# PAGE3-LED_Drivers.net
KiCad netlist of a schematic drawn in Altium Designer
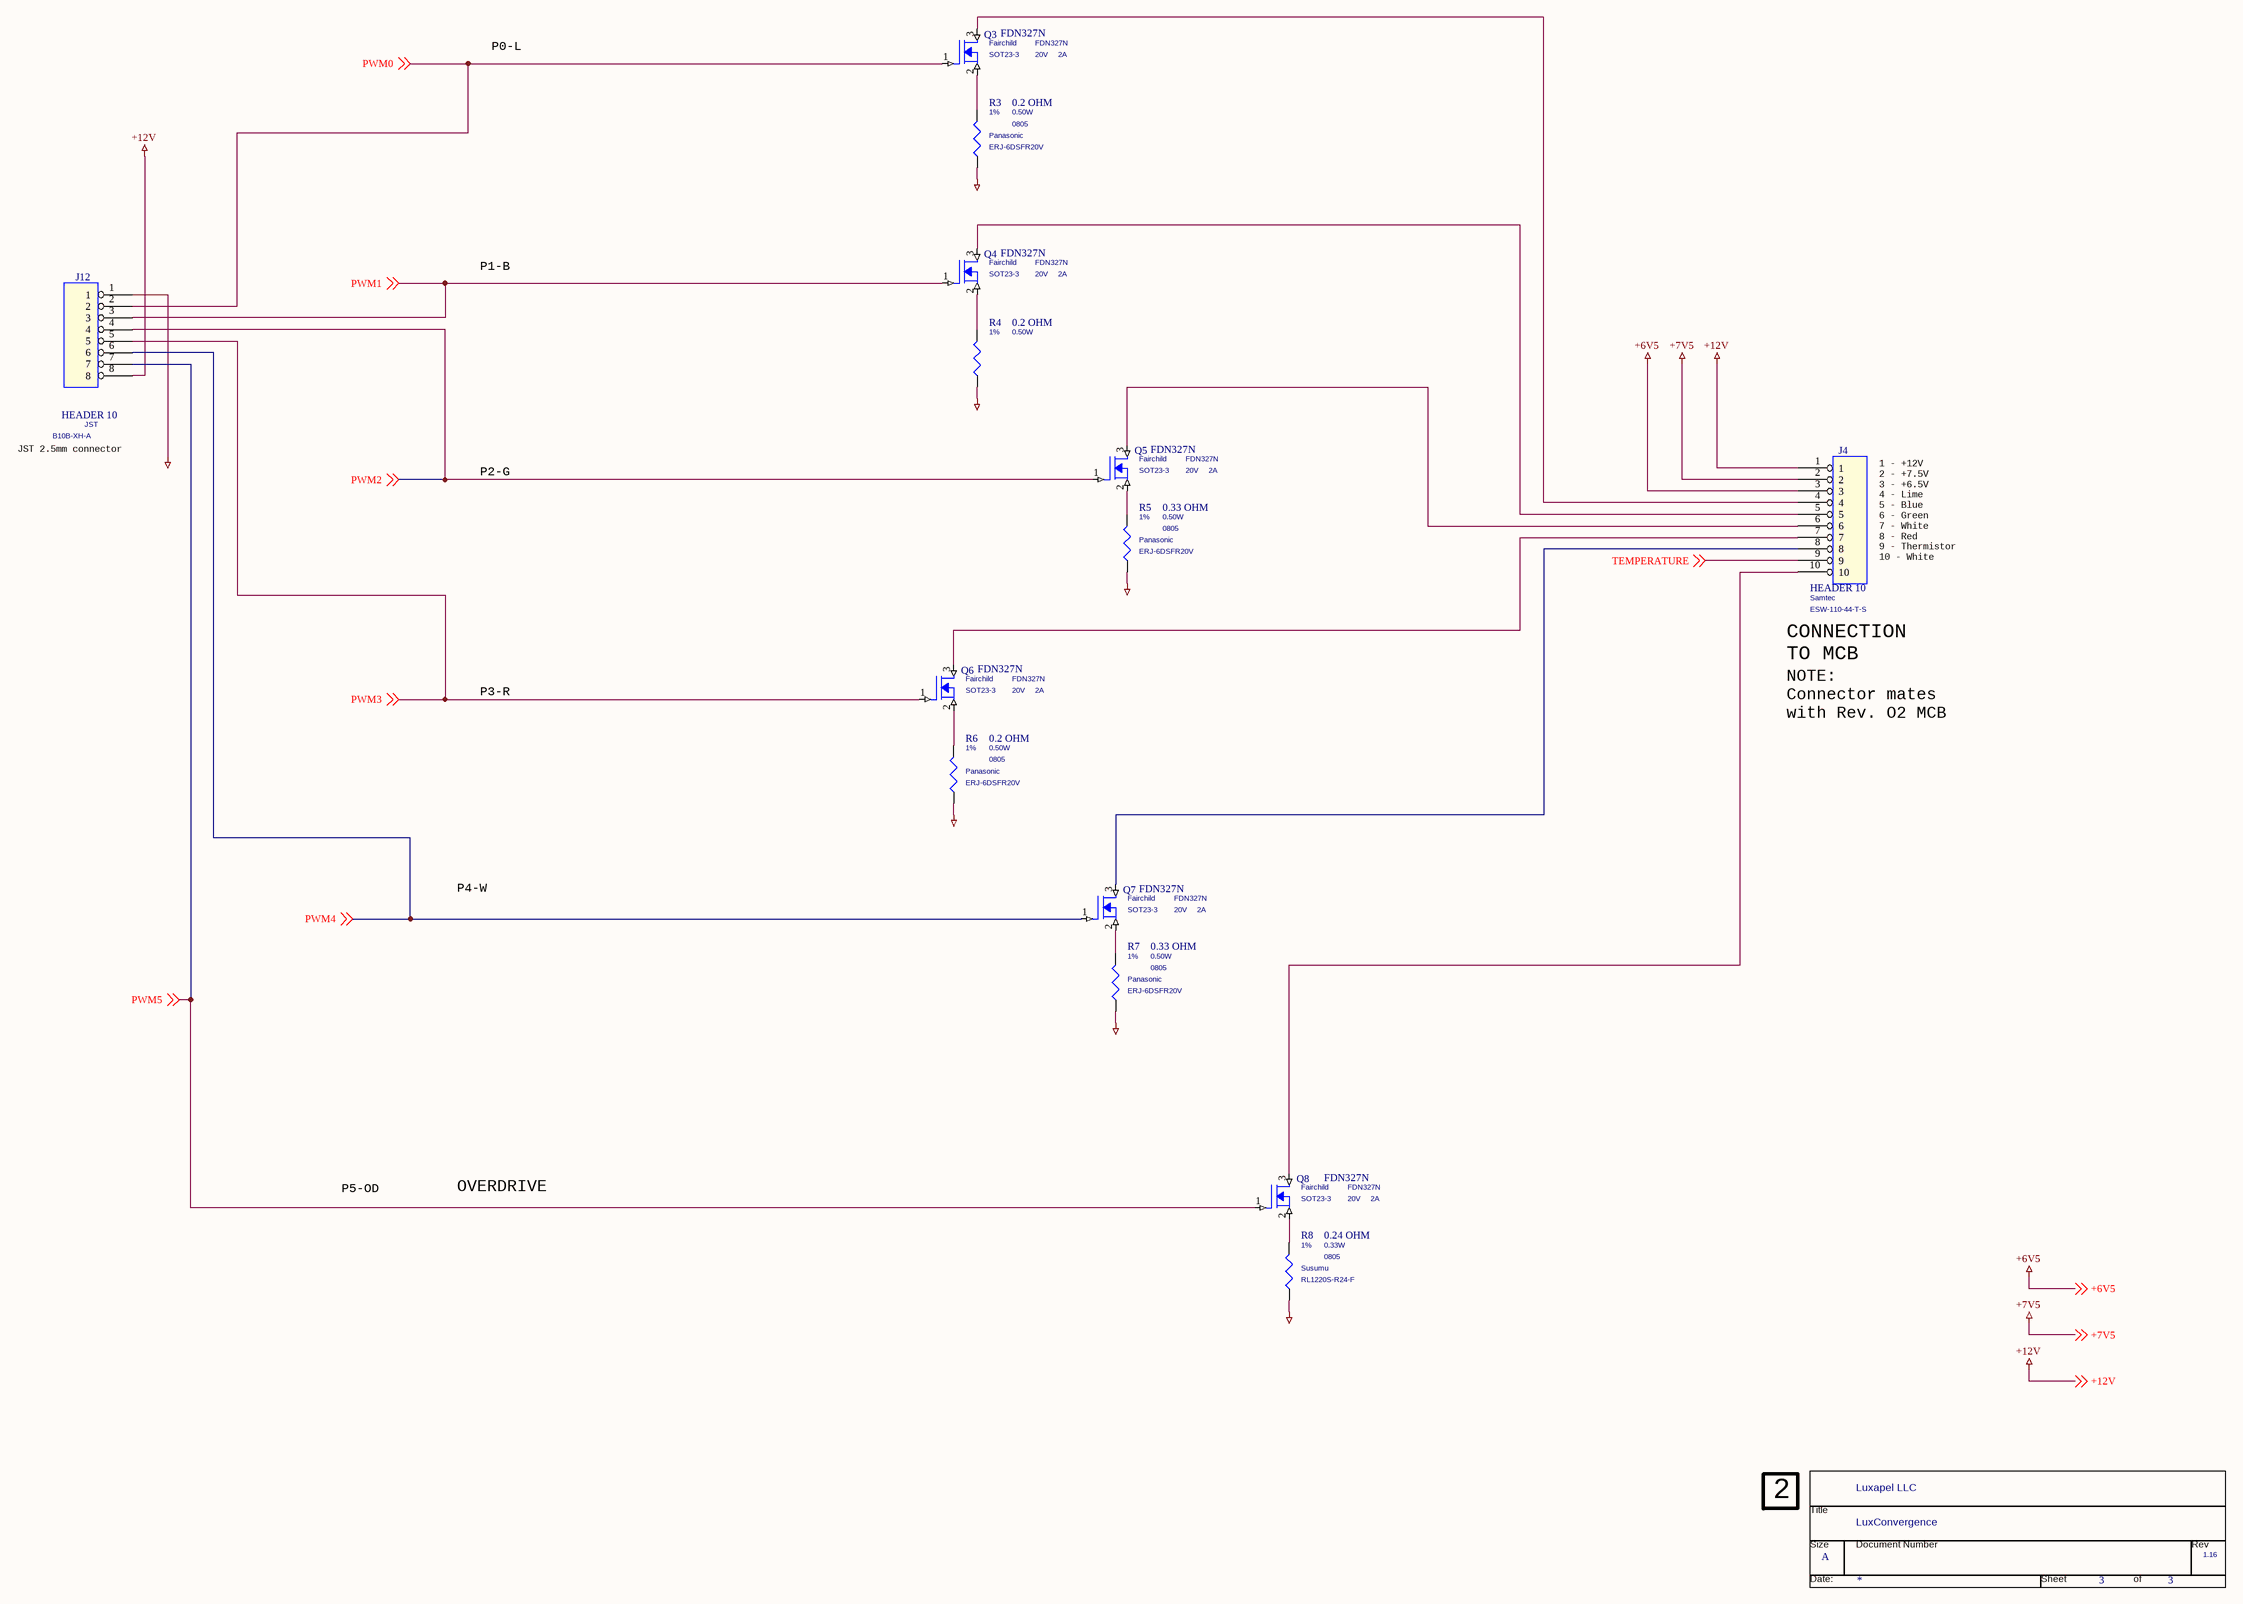
[diagram p0: PAGE3-LED_Drivers.SchDoc]

(export (version "E")
  (design (tool "Eeschema 10.0.6"))
  (components
    (comp (ref "J4")
      (value "HEADER 10")
      (footprint "SIP-10")
      (fields (field (name "MFG") "Samtec") (field (name "P/N") "ESW-110-44-T-S"))
      (libsource (lib "*") (part "HEADER 10"))
    )
    (comp (ref "J12")
      (value "HEADER 10")
      (footprint "SIP-10")
      (fields (field (name "MFG") "JST") (field (name "P/N") "B10B-XH-A"))
      (libsource (lib "*") (part "HEADER 10_0"))
    )
    (comp (ref "Q3")
      (value "FDN327N")
      (footprint "SOT23-3")
      (fields
        (field (name "VOLTAGE") "20V")
        (field (name "POWER") "2A")
        (field (name "P/N") "FDN327N")
        (field (name "MFG") "Fairchild")
        (field (name "PCB FOOTPRINT") "SOT23-3")
      )
      (libsource (lib "*") (part "N DGS_0"))
    )
    (comp (ref "Q4")
      (value "FDN327N")
      (footprint "SOT23-3")
      (fields
        (field (name "VOLTAGE") "20V")
        (field (name "POWER") "2A")
        (field (name "P/N") "FDN327N")
        (field (name "MFG") "Fairchild")
        (field (name "PCB FOOTPRINT") "SOT23-3")
      )
      (libsource (lib "*") (part "N DGS_0"))
    )
    (comp (ref "Q5")
      (value "FDN327N")
      (footprint "SOT23-3")
      (fields
        (field (name "MFG") "Fairchild")
        (field (name "P/N") "FDN327N")
        (field (name "POWER") "2A")
        (field (name "VOLTAGE") "20V")
        (field (name "PCB FOOTPRINT") "SOT23-3")
      )
      (libsource (lib "*") (part "N DGS_0"))
    )
    (comp (ref "Q6")
      (value "FDN327N")
      (footprint "SOT23-3")
      (fields
        (field (name "MFG") "Fairchild")
        (field (name "P/N") "FDN327N")
        (field (name "POWER") "2A")
        (field (name "VOLTAGE") "20V")
        (field (name "PCB FOOTPRINT") "SOT23-3")
      )
      (libsource (lib "*") (part "N DGS_0"))
    )
    (comp (ref "Q7")
      (value "FDN327N")
      (footprint "SOT23-323")
      (fields
        (field (name "MFG") "Fairchild")
        (field (name "P/N") "FDN327N")
        (field (name "POWER") "2A")
        (field (name "VOLTAGE") "20V")
        (field (name "PCB FOOTPRINT") "SOT23-3")
      )
      (libsource (lib "*") (part "N DGS_0"))
    )
    (comp (ref "Q8")
      (value "FDN327N")
      (footprint "SOT23-3")
      (fields
        (field (name "VOLTAGE") "20V")
        (field (name "POWER") "2A")
        (field (name "P/N") "FDN327N")
        (field (name "MFG") "Fairchild")
        (field (name "PCB FOOTPRINT") "SOT23-3")
      )
      (libsource (lib "*") (part "N DGS_0"))
    )
    (comp (ref "R3")
      (value "0.2 OHM")
      (footprint "0805")
      (fields
        (field (name "MFG") "Panasonic")
        (field (name "P/N") "ERJ-6DSFR20V")
        (field (name "PRECISION") "1%")
        (field (name "POWER") "0.50W")
        (field (name "VOLTAGE") "?V")
        (field (name "PCB FOOTPRINT") "0805")
      )
      (libsource (lib "*") (part "RESISTOR"))
    )
    (comp (ref "R4")
      (value "0.2 OHM")
      (footprint "1210")
      (fields
        (field (name "MFG") "Panasonic")
        (field (name "PRECISION") "1%")
        (field (name "POWER") "0.50W")
        (field (name "VOLTAGE") "?V")
      )
      (libsource (lib "*") (part "RESISTOR"))
    )
    (comp (ref "R5")
      (value "0.33 OHM")
      (footprint "_0805")
      (fields
        (field (name "MFG") "Panasonic")
        (field (name "P/N") "ERJ-6DSFR20V")
        (field (name "PRECISION") "1%")
        (field (name "POWER") "0.50W")
        (field (name "VOLTAGE") "?V")
        (field (name "PCB FOOTPRINT") "0805")
      )
      (libsource (lib "*") (part "RESISTOR"))
    )
    (comp (ref "R6")
      (value "0.2 OHM")
      (footprint "0805")
      (fields
        (field (name "MFG") "Panasonic")
        (field (name "P/N") "ERJ-6DSFR20V")
        (field (name "PRECISION") "1%")
        (field (name "POWER") "0.50W")
        (field (name "VOLTAGE") "?V")
        (field (name "PCB FOOTPRINT") "0805")
      )
      (libsource (lib "*") (part "RESISTOR"))
    )
    (comp (ref "R7")
      (value "0.33 OHM")
      (footprint "_0805")
      (fields
        (field (name "MFG") "Panasonic")
        (field (name "P/N") "ERJ-6DSFR20V")
        (field (name "PRECISION") "1%")
        (field (name "POWER") "0.50W")
        (field (name "VOLTAGE") "?V")
        (field (name "PCB FOOTPRINT") "0805")
      )
      (libsource (lib "*") (part "RESISTOR"))
    )
    (comp (ref "R8")
      (value "0.24 OHM")
      (footprint "0805")
      (fields
        (field (name "MFG") "Susumu")
        (field (name "P/N") "RL1220S-R24-F")
        (field (name "PRECISION") "1%")
        (field (name "POWER") "0.33W")
        (field (name "VOLTAGE") "?V")
        (field (name "PCB FOOTPRINT") "0805")
      )
      (libsource (lib "*") (part "RESISTOR"))
    )
  )
  (nets
    (net (code "1") (name "+6V5") (class "Default")
      (node (ref "J4") (pin "3") (pinfunction "3_3") (pintype "passive"))
    )
    (net (code "2") (name "+7V5") (class "Default")
      (node (ref "J4") (pin "2") (pinfunction "2_2") (pintype "passive"))
    )
    (net (code "3") (name "+12V") (class "Default")
      (node (ref "J12") (pin "8") (pinfunction "8_8") (pintype "passive"))
      (node (ref "J4") (pin "1") (pinfunction "1_1") (pintype "passive"))
    )
    (net (code "4") (name "GND_POWER.global") (class "Default")
      (node (ref "J12") (pin "1") (pinfunction "1_1") (pintype "passive"))
      (node (ref "R3") (pin "1") (pinfunction "1_1") (pintype "passive"))
      (node (ref "R4") (pin "1") (pinfunction "1_1") (pintype "passive"))
      (node (ref "R5") (pin "1") (pinfunction "1_1") (pintype "passive"))
      (node (ref "R6") (pin "1") (pinfunction "1_1") (pintype "passive"))
      (node (ref "R7") (pin "1") (pinfunction "1_1") (pintype "passive"))
      (node (ref "R8") (pin "1") (pinfunction "1_1") (pintype "passive"))
    )
    (net (code "5") (name "Net-(Q3-DRAIN)") (class "Default")
      (node (ref "J4") (pin "4") (pinfunction "4_4") (pintype "passive"))
      (node (ref "Q3") (pin "3") (pinfunction "DRAIN_3") (pintype "input"))
    )
    (net (code "6") (name "Net-(Q3-SOURCE)") (class "Default")
      (node (ref "Q3") (pin "2") (pinfunction "SOURCE_2") (pintype "input"))
      (node (ref "R3") (pin "2") (pinfunction "2_2") (pintype "passive"))
    )
    (net (code "7") (name "Net-(Q4-DRAIN)") (class "Default")
      (node (ref "J4") (pin "5") (pinfunction "5_5") (pintype "passive"))
      (node (ref "Q4") (pin "3") (pinfunction "DRAIN_3") (pintype "input"))
    )
    (net (code "8") (name "Net-(Q4-SOURCE)") (class "Default")
      (node (ref "Q4") (pin "2") (pinfunction "SOURCE_2") (pintype "input"))
      (node (ref "R4") (pin "2") (pinfunction "2_2") (pintype "passive"))
    )
    (net (code "9") (name "Net-(Q5-DRAIN)") (class "Default")
      (node (ref "J4") (pin "6") (pinfunction "6_6") (pintype "passive"))
      (node (ref "Q5") (pin "3") (pinfunction "DRAIN_3") (pintype "input"))
    )
    (net (code "10") (name "Net-(Q5-SOURCE)") (class "Default")
      (node (ref "Q5") (pin "2") (pinfunction "SOURCE_2") (pintype "input"))
      (node (ref "R5") (pin "2") (pinfunction "2_2") (pintype "passive"))
    )
    (net (code "11") (name "Net-(Q6-DRAIN)") (class "Default")
      (node (ref "J4") (pin "7") (pinfunction "7_7") (pintype "passive"))
      (node (ref "Q6") (pin "3") (pinfunction "DRAIN_3") (pintype "input"))
    )
    (net (code "12") (name "Net-(Q6-SOURCE)") (class "Default")
      (node (ref "Q6") (pin "2") (pinfunction "SOURCE_2") (pintype "input"))
      (node (ref "R6") (pin "2") (pinfunction "2_2") (pintype "passive"))
    )
    (net (code "13") (name "Net-(Q7-DRAIN)") (class "Default")
      (node (ref "J4") (pin "8") (pinfunction "8_8") (pintype "passive"))
      (node (ref "Q7") (pin "3") (pinfunction "DRAIN_3") (pintype "input"))
    )
    (net (code "14") (name "Net-(Q7-SOURCE)") (class "Default")
      (node (ref "Q7") (pin "2") (pinfunction "SOURCE_2") (pintype "input"))
      (node (ref "R7") (pin "2") (pinfunction "2_2") (pintype "passive"))
    )
    (net (code "15") (name "Net-(Q8-DRAIN)") (class "Default")
      (node (ref "J4") (pin "10") (pinfunction "10_10") (pintype "passive"))
      (node (ref "Q8") (pin "3") (pinfunction "DRAIN_3") (pintype "input"))
    )
    (net (code "16") (name "Net-(Q8-SOURCE)") (class "Default")
      (node (ref "Q8") (pin "2") (pinfunction "SOURCE_2") (pintype "input"))
      (node (ref "R8") (pin "2") (pinfunction "2_2") (pintype "passive"))
    )
    (net (code "17") (name "PWM0") (class "Default")
      (node (ref "J12") (pin "2") (pinfunction "2_2") (pintype "passive"))
      (node (ref "Q3") (pin "1") (pinfunction "GATE_1") (pintype "input"))
    )
    (net (code "18") (name "PWM1") (class "Default")
      (node (ref "J12") (pin "3") (pinfunction "3_3") (pintype "passive"))
      (node (ref "Q4") (pin "1") (pinfunction "GATE_1") (pintype "input"))
    )
    (net (code "19") (name "PWM2") (class "Default")
      (node (ref "J12") (pin "4") (pinfunction "4_4") (pintype "passive"))
      (node (ref "Q5") (pin "1") (pinfunction "GATE_1") (pintype "input"))
    )
    (net (code "20") (name "PWM3") (class "Default")
      (node (ref "J12") (pin "5") (pinfunction "5_5") (pintype "passive"))
      (node (ref "Q6") (pin "1") (pinfunction "GATE_1") (pintype "input"))
    )
    (net (code "21") (name "PWM4") (class "Default")
      (node (ref "J12") (pin "6") (pinfunction "6_6") (pintype "passive"))
      (node (ref "Q7") (pin "1") (pinfunction "GATE_1") (pintype "input"))
    )
    (net (code "22") (name "PWM5") (class "Default")
      (node (ref "J12") (pin "7") (pinfunction "7_7") (pintype "passive"))
      (node (ref "Q8") (pin "1") (pinfunction "GATE_1") (pintype "input"))
    )
    (net (code "23") (name "TEMPERATURE") (class "Default")
      (node (ref "J4") (pin "9") (pinfunction "9_9") (pintype "passive"))
    )
  )
)
